# Main_board.net
KiCad netlist of a schematic drawn in EAGLE
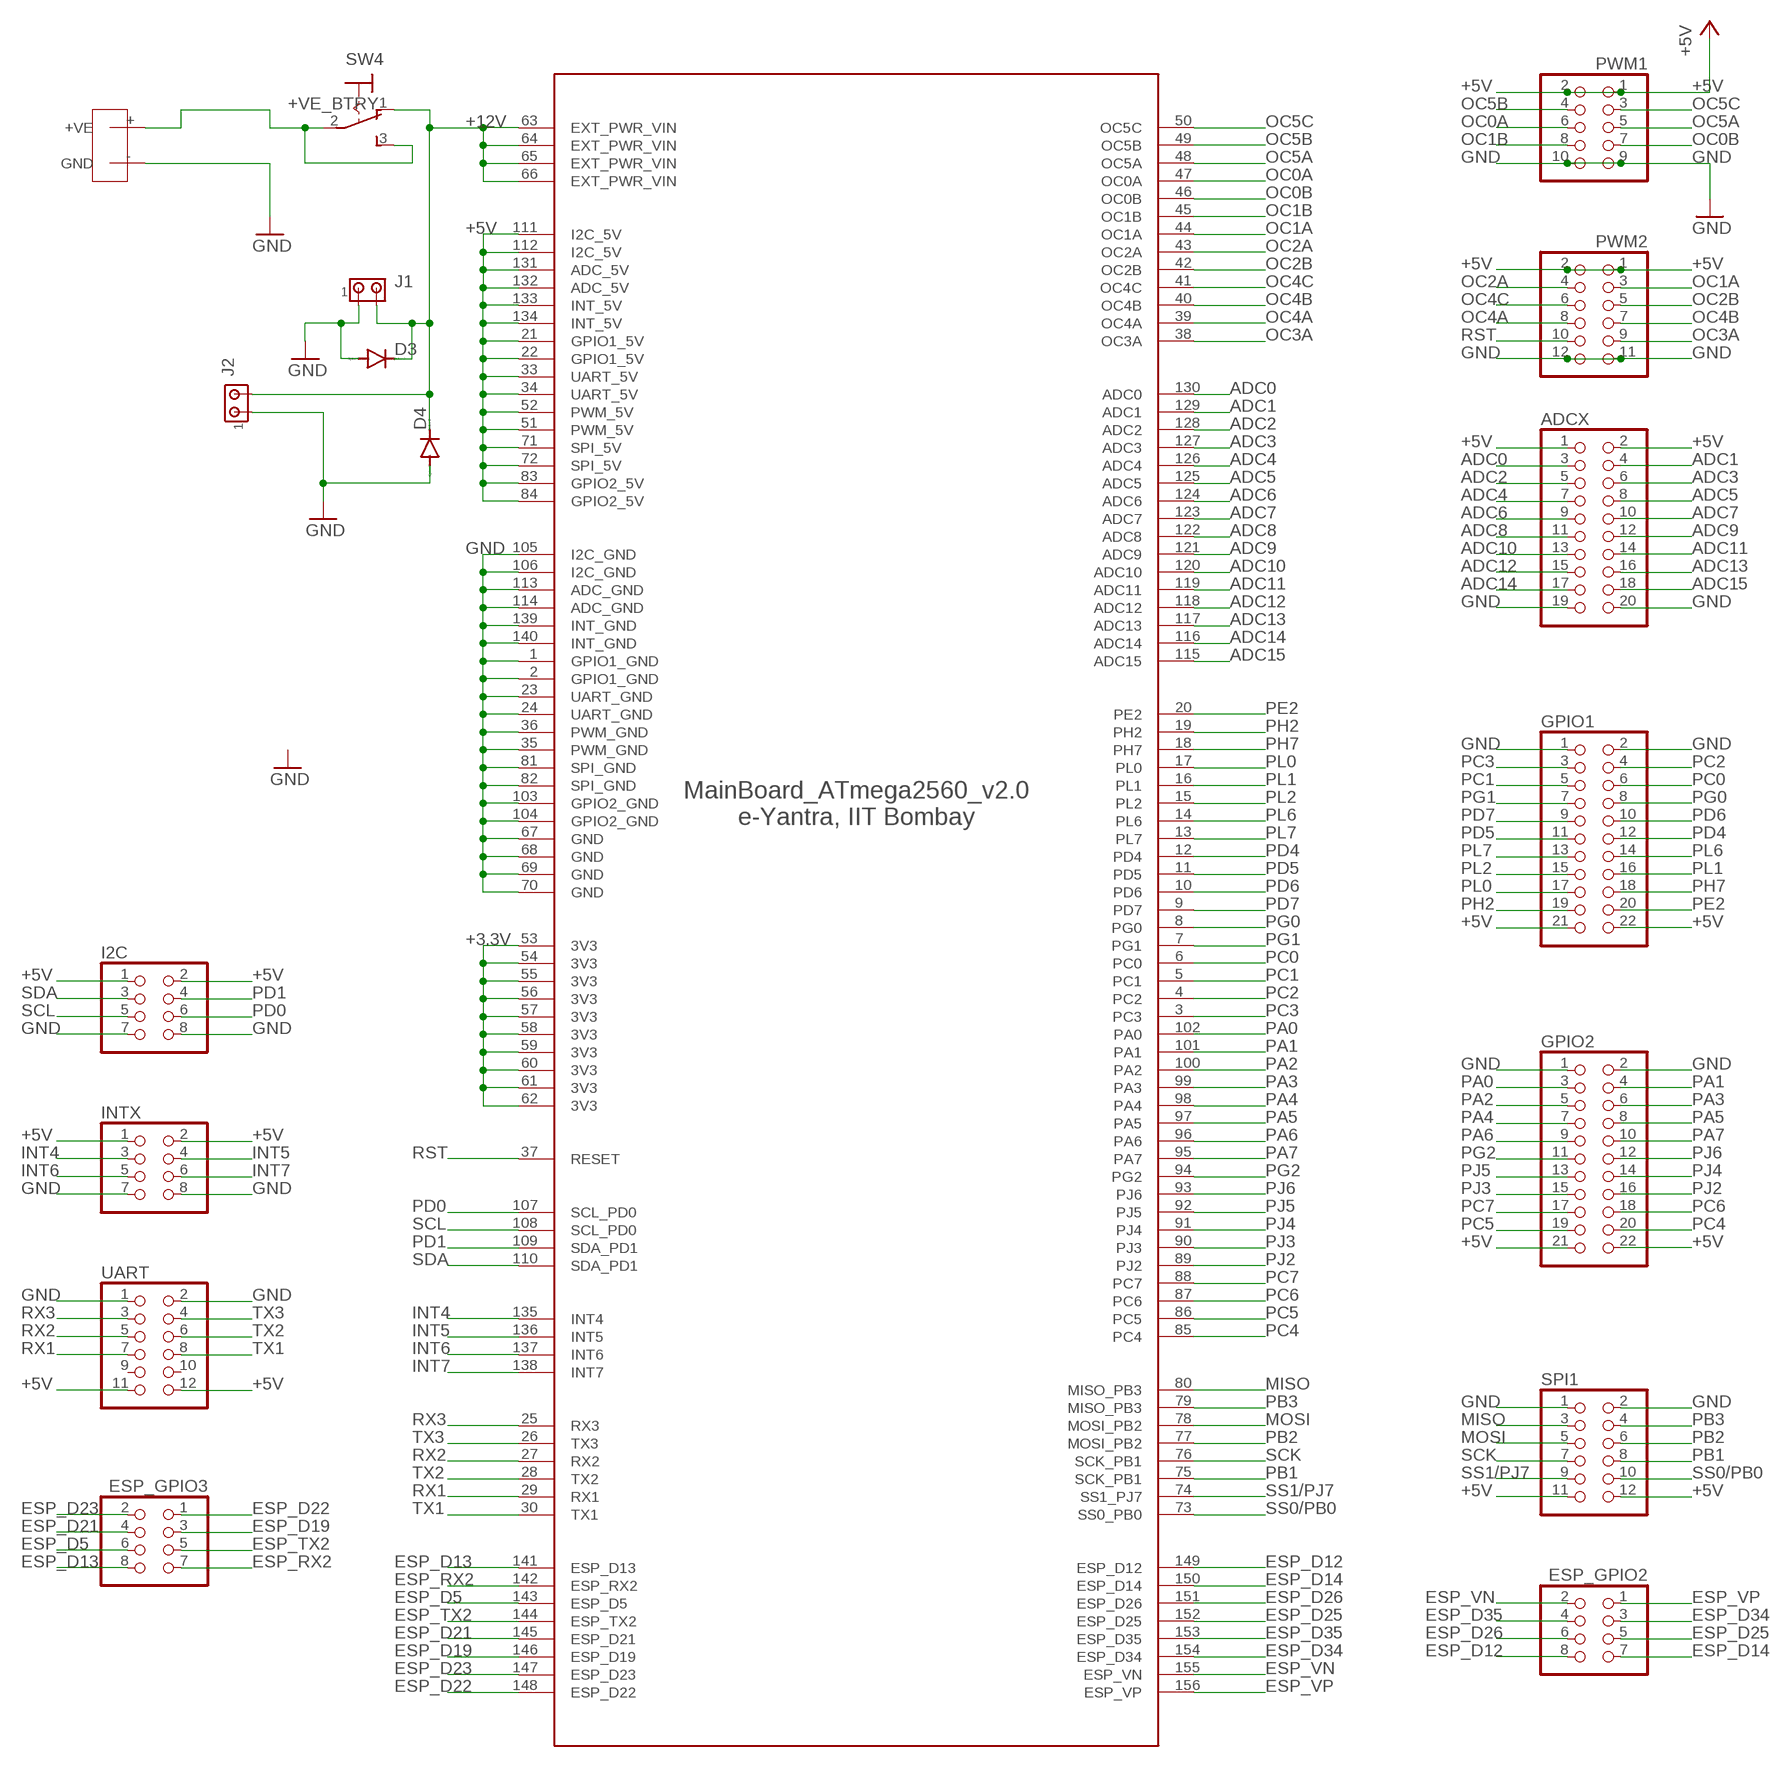
[diagram p0: schematic, sheet 1]
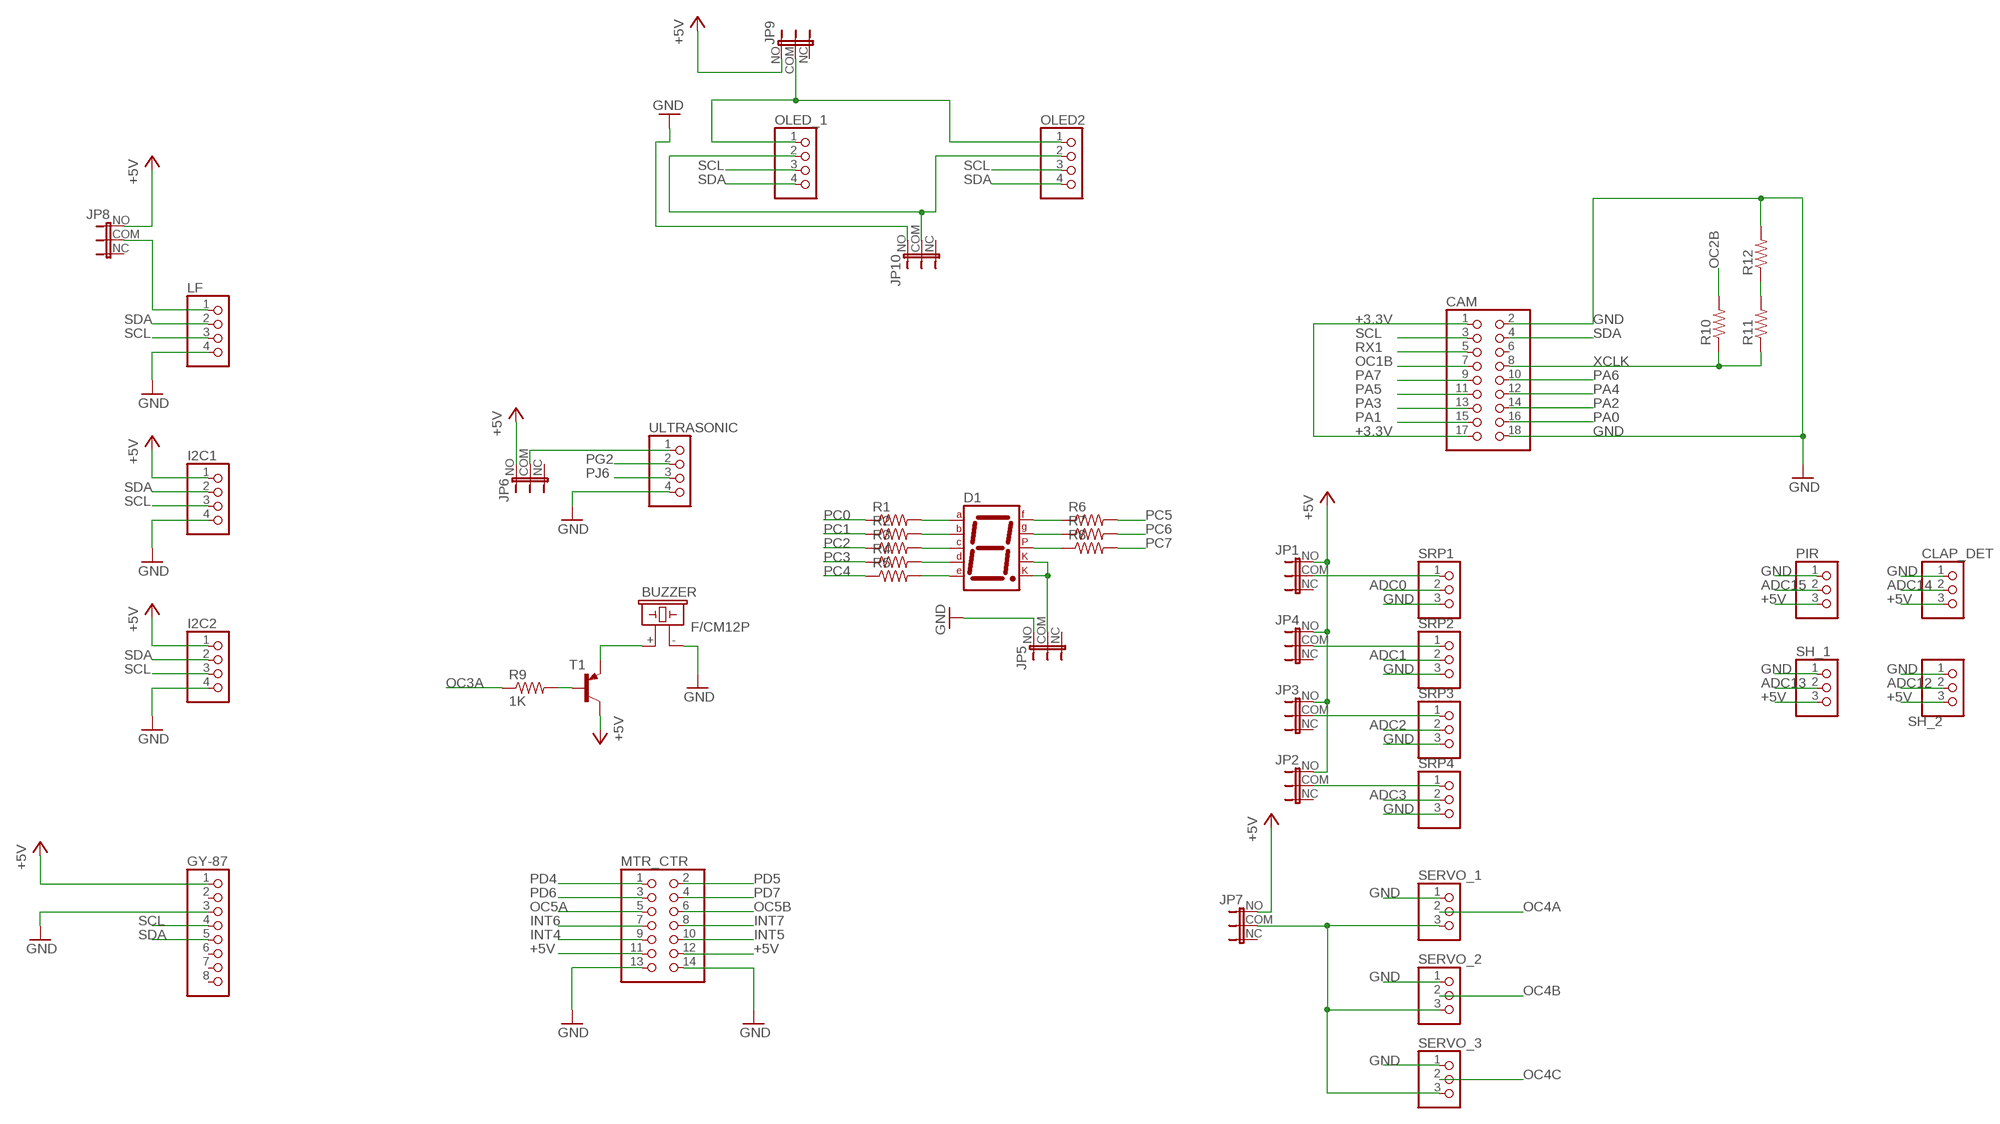
[diagram p1: schematic, sheet 2]

(export (version "E")
  (design (tool "Eeschema 10.0.6"))
  (components
    (comp (ref "BUZZER")
      (value "F/CM12P")
      (footprint "eagle-import:F_CM12P")
      (libsource (lib "eagle-import") (part "F/CM12P"))
    )
    (comp (ref "CAM")
      (value "PINHD-2X9")
      (footprint "eagle-import:2X09")
      (libsource (lib "eagle-import") (part "PINHD-2X9"))
    )
    (comp (ref "CLAP_DET")
      (value "PINHD-1X3")
      (footprint "eagle-import:1X03")
      (libsource (lib "eagle-import") (part "pinhead_325_PINHD-1X3"))
    )
    (comp (ref "D1")
      (value "7SEG-CK")
      (footprint "eagle-import:7SEG-13")
      (libsource (lib "eagle-import") (part "7SEG-CK"))
    )
    (comp (ref "GY-87")
      (value "PINHD-1X8")
      (footprint "eagle-import:1X08")
      (libsource (lib "eagle-import") (part "PINHD-1X8"))
    )
    (comp (ref "I2C1")
      (value "PINHD-1X4")
      (footprint "eagle-import:1X04")
      (libsource (lib "eagle-import") (part "PINHD-1X4"))
    )
    (comp (ref "I2C2")
      (value "PINHD-1X4")
      (footprint "eagle-import:1X04")
      (libsource (lib "eagle-import") (part "PINHD-1X4"))
    )
    (comp (ref "JP1")
      (value "JP2E")
      (footprint "eagle-import:JP2")
      (libsource (lib "eagle-import") (part "JP2E"))
    )
    (comp (ref "JP2")
      (value "JP2E")
      (footprint "eagle-import:JP2")
      (libsource (lib "eagle-import") (part "JP2E"))
    )
    (comp (ref "JP3")
      (value "JP2E")
      (footprint "eagle-import:JP2")
      (libsource (lib "eagle-import") (part "JP2E"))
    )
    (comp (ref "JP4")
      (value "JP2E")
      (footprint "eagle-import:JP2")
      (libsource (lib "eagle-import") (part "JP2E"))
    )
    (comp (ref "JP5")
      (value "JP2E")
      (footprint "eagle-import:JP2")
      (libsource (lib "eagle-import") (part "JP2E"))
    )
    (comp (ref "JP6")
      (value "JP2E")
      (footprint "eagle-import:JP2")
      (libsource (lib "eagle-import") (part "JP2E"))
    )
    (comp (ref "JP7")
      (value "JP2E")
      (footprint "eagle-import:JP2")
      (libsource (lib "eagle-import") (part "JP2E"))
    )
    (comp (ref "JP8")
      (value "JP2E")
      (footprint "eagle-import:JP2")
      (libsource (lib "eagle-import") (part "JP2E"))
    )
    (comp (ref "JP9")
      (value "JP2E")
      (footprint "eagle-import:JP2")
      (libsource (lib "eagle-import") (part "JP2E"))
    )
    (comp (ref "JP10")
      (value "JP2E")
      (footprint "eagle-import:JP2")
      (libsource (lib "eagle-import") (part "JP2E"))
    )
    (comp (ref "LF")
      (value "PINHD-1X4")
      (footprint "eagle-import:1X04")
      (libsource (lib "eagle-import") (part "PINHD-1X4"))
    )
    (comp (ref "MTR_CTR")
      (value "PINHD-2X7")
      (footprint "eagle-import:2X07")
      (libsource (lib "eagle-import") (part "PINHD-2X7"))
    )
    (comp (ref "OLED2")
      (value "PINHD-1X4")
      (footprint "eagle-import:1X04")
      (libsource (lib "eagle-import") (part "PINHD-1X4"))
    )
    (comp (ref "OLED_1")
      (value "PINHD-1X4")
      (footprint "eagle-import:1X04")
      (libsource (lib "eagle-import") (part "PINHD-1X4"))
    )
    (comp (ref "PIR")
      (value "PINHD-1X3")
      (footprint "eagle-import:1X03")
      (libsource (lib "eagle-import") (part "pinhead_325_PINHD-1X3"))
    )
    (comp (ref "R1")
      (value "R-US_R1206")
      (footprint "eagle-import:R1206")
      (libsource (lib "eagle-import") (part "R-US_R1206"))
    )
    (comp (ref "R2")
      (value "R-US_R1206")
      (footprint "eagle-import:R1206")
      (libsource (lib "eagle-import") (part "R-US_R1206"))
    )
    (comp (ref "R3")
      (value "R-US_R1206")
      (footprint "eagle-import:R1206")
      (libsource (lib "eagle-import") (part "R-US_R1206"))
    )
    (comp (ref "R4")
      (value "R-US_R1206")
      (footprint "eagle-import:R1206")
      (libsource (lib "eagle-import") (part "R-US_R1206"))
    )
    (comp (ref "R5")
      (value "R-US_R1206")
      (footprint "eagle-import:R1206")
      (libsource (lib "eagle-import") (part "R-US_R1206"))
    )
    (comp (ref "R6")
      (value "R-US_R1206")
      (footprint "eagle-import:R1206")
      (libsource (lib "eagle-import") (part "R-US_R1206"))
    )
    (comp (ref "R7")
      (value "R-US_R1206")
      (footprint "eagle-import:R1206")
      (libsource (lib "eagle-import") (part "R-US_R1206"))
    )
    (comp (ref "R8")
      (value "R-US_R1206")
      (footprint "eagle-import:R1206")
      (libsource (lib "eagle-import") (part "R-US_R1206"))
    )
    (comp (ref "R9")
      (value "1K")
      (footprint "eagle-import:R1206")
      (libsource (lib "eagle-import") (part "R-US_R1206"))
    )
    (comp (ref "R10")
      (value "R-US_R1206")
      (footprint "eagle-import:R1206")
      (libsource (lib "eagle-import") (part "R-US_R1206"))
    )
    (comp (ref "R11")
      (value "R-US_R1206")
      (footprint "eagle-import:R1206")
      (libsource (lib "eagle-import") (part "R-US_R1206"))
    )
    (comp (ref "R12")
      (value "R-US_R1206")
      (footprint "eagle-import:R1206")
      (libsource (lib "eagle-import") (part "R-US_R1206"))
    )
    (comp (ref "SERVO_1")
      (value "PINHD-1X3")
      (footprint "eagle-import:1X03")
      (libsource (lib "eagle-import") (part "pinhead_325_PINHD-1X3"))
    )
    (comp (ref "SERVO_2")
      (value "PINHD-1X3")
      (footprint "eagle-import:1X03")
      (libsource (lib "eagle-import") (part "pinhead_325_PINHD-1X3"))
    )
    (comp (ref "SERVO_3")
      (value "PINHD-1X3")
      (footprint "eagle-import:1X03")
      (libsource (lib "eagle-import") (part "pinhead_325_PINHD-1X3"))
    )
    (comp (ref "SH_1")
      (value "PINHD-1X3")
      (footprint "eagle-import:1X03")
      (libsource (lib "eagle-import") (part "pinhead_325_PINHD-1X3"))
    )
    (comp (ref "SH_2")
      (value "PINHD-1X3")
      (footprint "eagle-import:1X03")
      (libsource (lib "eagle-import") (part "pinhead_325_PINHD-1X3"))
    )
    (comp (ref "SRP1")
      (value "PINHD-1X3")
      (footprint "eagle-import:1X03")
      (libsource (lib "eagle-import") (part "PINHD-1X3"))
    )
    (comp (ref "SRP2")
      (value "PINHD-1X3")
      (footprint "eagle-import:1X03")
      (libsource (lib "eagle-import") (part "PINHD-1X3"))
    )
    (comp (ref "SRP3")
      (value "PINHD-1X3")
      (footprint "eagle-import:1X03")
      (libsource (lib "eagle-import") (part "PINHD-1X3"))
    )
    (comp (ref "SRP4")
      (value "PINHD-1X3")
      (footprint "eagle-import:1X03")
      (libsource (lib "eagle-import") (part "PINHD-1X3"))
    )
    (comp (ref "T1")
      (value "BC807-16-PNP-SOT23-BEC")
      (footprint "eagle-import:SOT23-BEC")
      (libsource (lib "eagle-import") (part "-PNP-SOT23-BECBC807-16"))
    )
    (comp (ref "ULTRASONIC")
      (value "PINHD-1X4")
      (footprint "eagle-import:1X04")
      (libsource (lib "eagle-import") (part "PINHD-1X4"))
    )
    (comp (ref "ADCX")
      (value "PINHD-2X10")
      (footprint "eagle-import:2X10")
      (libsource (lib "eagle-import") (part "PINHD-2X10"))
    )
    (comp (ref "D3")
      (value "DIODE-DO214AC")
      (footprint "eagle-import:DO214AC")
      (libsource (lib "eagle-import") (part "DIODE-DO214AC"))
    )
    (comp (ref "D4")
      (value "DIODE-DO214AC")
      (footprint "eagle-import:DO214AC")
      (libsource (lib "eagle-import") (part "DIODE-DO214AC"))
    )
    (comp (ref "ESP_GPIO2")
      (value "PINHD-2X4")
      (footprint "eagle-import:2X04")
      (libsource (lib "eagle-import") (part "PINHD-2X4"))
    )
    (comp (ref "ESP_GPIO3")
      (value "PINHD-2X4")
      (footprint "eagle-import:2X04")
      (libsource (lib "eagle-import") (part "PINHD-2X4"))
    )
    (comp (ref "EYFI_MEGA")
      (value "ATMEGA2560_V2.0")
      (footprint "eagle-import:ATMEGA2560_V2.0")
      (libsource (lib "eagle-import") (part "ATMEGA2560_V2.0"))
    )
    (comp (ref "GPIO1")
      (value "PINHD-2X11")
      (footprint "eagle-import:2X11")
      (libsource (lib "eagle-import") (part "PINHD-2X11"))
    )
    (comp (ref "GPIO2")
      (value "PINHD-2X11")
      (footprint "eagle-import:2X11")
      (libsource (lib "eagle-import") (part "PINHD-2X11"))
    )
    (comp (ref "I2C")
      (value "PINHD-2X4")
      (footprint "eagle-import:2X04")
      (libsource (lib "eagle-import") (part "PINHD-2X4"))
    )
    (comp (ref "INTX")
      (value "PINHD-2X4")
      (footprint "eagle-import:2X04")
      (libsource (lib "eagle-import") (part "PINHD-2X4"))
    )
    (comp (ref "J1")
      (value "MTA02-156")
      (footprint "eagle-import:1X2MTA")
      (libsource (lib "eagle-import") (part "MTA02-156"))
    )
    (comp (ref "J2")
      (value "MTA02-156")
      (footprint "eagle-import:1X2MTA")
      (libsource (lib "eagle-import") (part "MTA02-156"))
    )
    (comp (ref "PWM1")
      (value "PINHD-2X5")
      (footprint "eagle-import:2X05")
      (libsource (lib "eagle-import") (part "PINHD-2X5"))
    )
    (comp (ref "PWM2")
      (value "PINHD-2X6")
      (footprint "eagle-import:2X06")
      (libsource (lib "eagle-import") (part "PINHD-2X6"))
    )
    (comp (ref "SPI1")
      (value "PINHD-2X6")
      (footprint "eagle-import:2X06")
      (libsource (lib "eagle-import") (part "PINHD-2X6"))
    )
    (comp (ref "SW4")
      (value "M9040P")
      (footprint "eagle-import:M9040P")
      (libsource (lib "eagle-import") (part "M9040P"))
    )
    (comp (ref "U$1")
      (value "DEANS")
      (footprint "eagle-import:DEANS")
      (libsource (lib "eagle-import") (part "DEANS"))
    )
    (comp (ref "UART")
      (value "PINHD-2X6")
      (footprint "eagle-import:2X06")
      (libsource (lib "eagle-import") (part "PINHD-2X6"))
    )
  )
  (nets
    (net (code "1") (name "+3.3V") (class "Default")
      (node (ref "CAM") (pin "1") (pinfunction "1_1") (pintype "passive"))
      (node (ref "CAM") (pin "17") (pinfunction "17_17") (pintype "passive"))
      (node (ref "EYFI_MEGA") (pin "53") (pinfunction "3V3_53") (pintype "power_in"))
      (node (ref "EYFI_MEGA") (pin "54") (pinfunction "3V3_54") (pintype "power_in"))
      (node (ref "EYFI_MEGA") (pin "55") (pinfunction "3V3_55") (pintype "power_in"))
      (node (ref "EYFI_MEGA") (pin "56") (pinfunction "3V3_56") (pintype "power_in"))
      (node (ref "EYFI_MEGA") (pin "57") (pinfunction "3V3_57") (pintype "power_in"))
      (node (ref "EYFI_MEGA") (pin "58") (pinfunction "3V3_58") (pintype "power_in"))
      (node (ref "EYFI_MEGA") (pin "59") (pinfunction "3V3_59") (pintype "power_in"))
      (node (ref "EYFI_MEGA") (pin "60") (pinfunction "3V3_60") (pintype "power_in"))
      (node (ref "EYFI_MEGA") (pin "61") (pinfunction "3V3_61") (pintype "power_in"))
      (node (ref "EYFI_MEGA") (pin "62") (pinfunction "3V3_62") (pintype "power_in"))
    )
    (net (code "2") (name "+5V") (class "Default")
      (node (ref "ADCX") (pin "1") (pinfunction "1_1") (pintype "passive"))
      (node (ref "ADCX") (pin "2") (pinfunction "2_2") (pintype "passive"))
      (node (ref "CLAP_DET") (pin "3") (pinfunction "3_3") (pintype "passive"))
      (node (ref "EYFI_MEGA") (pin "111") (pinfunction "I2C_5V_111") (pintype "power_in"))
      (node (ref "EYFI_MEGA") (pin "112") (pinfunction "I2C_5V_112") (pintype "power_in"))
      (node (ref "EYFI_MEGA") (pin "131") (pinfunction "ADC_5V_131") (pintype "power_in"))
      (node (ref "EYFI_MEGA") (pin "132") (pinfunction "ADC_5V_132") (pintype "power_in"))
      (node (ref "EYFI_MEGA") (pin "133") (pinfunction "INT_5V_133") (pintype "power_in"))
      (node (ref "EYFI_MEGA") (pin "134") (pinfunction "INT_5V_134") (pintype "power_in"))
      (node (ref "EYFI_MEGA") (pin "21") (pinfunction "GPIO1_5V_21") (pintype "power_in"))
      (node (ref "EYFI_MEGA") (pin "22") (pinfunction "GPIO1_5V_22") (pintype "power_in"))
      (node (ref "EYFI_MEGA") (pin "33") (pinfunction "UART_5V_33") (pintype "power_in"))
      (node (ref "EYFI_MEGA") (pin "34") (pinfunction "UART_5V_34") (pintype "power_in"))
      (node (ref "EYFI_MEGA") (pin "51") (pinfunction "PWM_5V_51") (pintype "power_in"))
      (node (ref "EYFI_MEGA") (pin "52") (pinfunction "PWM_5V_52") (pintype "power_in"))
      (node (ref "EYFI_MEGA") (pin "71") (pinfunction "SPI_5V_71") (pintype "power_in"))
      (node (ref "EYFI_MEGA") (pin "72") (pinfunction "SPI_5V_72") (pintype "power_in"))
      (node (ref "EYFI_MEGA") (pin "83") (pinfunction "GPIO2_5V_83") (pintype "power_in"))
      (node (ref "EYFI_MEGA") (pin "84") (pinfunction "GPIO2_5V_84") (pintype "power_in"))
      (node (ref "GPIO1") (pin "21") (pinfunction "21_21") (pintype "passive"))
      (node (ref "GPIO1") (pin "22") (pinfunction "22_22") (pintype "passive"))
      (node (ref "GPIO2") (pin "21") (pinfunction "21_21") (pintype "passive"))
      (node (ref "GPIO2") (pin "22") (pinfunction "22_22") (pintype "passive"))
      (node (ref "GY-87") (pin "1") (pinfunction "1_1") (pintype "passive"))
      (node (ref "I2C") (pin "1") (pinfunction "1_1") (pintype "passive"))
      (node (ref "I2C") (pin "2") (pinfunction "2_2") (pintype "passive"))
      (node (ref "I2C1") (pin "1") (pinfunction "1_1") (pintype "passive"))
      (node (ref "I2C2") (pin "1") (pinfunction "1_1") (pintype "passive"))
      (node (ref "INTX") (pin "1") (pinfunction "1_1") (pintype "passive"))
      (node (ref "INTX") (pin "2") (pinfunction "2_2") (pintype "passive"))
      (node (ref "JP1") (pin "NO") (pinfunction "1_NO") (pintype "passive"))
      (node (ref "JP2") (pin "NO") (pinfunction "1_NO") (pintype "passive"))
      (node (ref "JP3") (pin "NO") (pinfunction "1_NO") (pintype "passive"))
      (node (ref "JP4") (pin "NO") (pinfunction "1_NO") (pintype "passive"))
      (node (ref "JP6") (pin "NO") (pinfunction "1_NO") (pintype "passive"))
      (node (ref "JP7") (pin "NO") (pinfunction "1_NO") (pintype "passive"))
      (node (ref "JP8") (pin "NO") (pinfunction "1_NO") (pintype "passive"))
      (node (ref "JP9") (pin "NO") (pinfunction "1_NO") (pintype "passive"))
      (node (ref "MTR_CTR") (pin "11") (pinfunction "11_11") (pintype "passive"))
      (node (ref "MTR_CTR") (pin "12") (pinfunction "12_12") (pintype "passive"))
      (node (ref "PIR") (pin "3") (pinfunction "3_3") (pintype "passive"))
      (node (ref "PWM1") (pin "1") (pinfunction "1_1") (pintype "passive"))
      (node (ref "PWM1") (pin "2") (pinfunction "2_2") (pintype "passive"))
      (node (ref "PWM2") (pin "1") (pinfunction "1_1") (pintype "passive"))
      (node (ref "PWM2") (pin "2") (pinfunction "2_2") (pintype "passive"))
      (node (ref "SH_1") (pin "3") (pinfunction "3_3") (pintype "passive"))
      (node (ref "SH_2") (pin "3") (pinfunction "3_3") (pintype "passive"))
      (node (ref "SPI1") (pin "11") (pinfunction "11_11") (pintype "passive"))
      (node (ref "SPI1") (pin "12") (pinfunction "12_12") (pintype "passive"))
      (node (ref "T1") (pin "C") (pinfunction "C_C") (pintype "passive"))
      (node (ref "UART") (pin "11") (pinfunction "11_11") (pintype "passive"))
      (node (ref "UART") (pin "12") (pinfunction "12_12") (pintype "passive"))
    )
    (net (code "3") (name "+12V") (class "Default")
      (node (ref "D3") (pin "C") (pinfunction "C_C") (pintype "passive"))
      (node (ref "D4") (pin "C") (pinfunction "C_C") (pintype "passive"))
      (node (ref "EYFI_MEGA") (pin "63") (pinfunction "EXT_PWR_VIN_63") (pintype "power_in"))
      (node (ref "EYFI_MEGA") (pin "64") (pinfunction "EXT_PWR_VIN_64") (pintype "power_in"))
      (node (ref "EYFI_MEGA") (pin "65") (pinfunction "EXT_PWR_VIN_65") (pintype "power_in"))
      (node (ref "EYFI_MEGA") (pin "66") (pinfunction "EXT_PWR_VIN_66") (pintype "power_in"))
      (node (ref "J1") (pin "2") (pinfunction "2_2") (pintype "passive"))
      (node (ref "J2") (pin "2") (pinfunction "2_2") (pintype "passive"))
      (node (ref "SW4") (pin "1") (pinfunction "O_1") (pintype "passive"))
    )
    (net (code "4") (name "+VE_BTRY") (class "Default")
      (node (ref "SW4") (pin "2") (pinfunction "P_2") (pintype "passive"))
      (node (ref "SW4") (pin "3") (pinfunction "S_3") (pintype "passive"))
      (node (ref "U$1") (pin "+") (pinfunction "+VE_+") (pintype "bidirectional"))
    )
    (net (code "5") (name "ADC0") (class "Default")
      (node (ref "ADCX") (pin "3") (pinfunction "3_3") (pintype "passive"))
      (node (ref "EYFI_MEGA") (pin "130") (pinfunction "ADC0_130") (pintype "bidirectional"))
      (node (ref "SRP1") (pin "2") (pinfunction "2_2") (pintype "passive"))
    )
    (net (code "6") (name "ADC1") (class "Default")
      (node (ref "ADCX") (pin "4") (pinfunction "4_4") (pintype "passive"))
      (node (ref "EYFI_MEGA") (pin "129") (pinfunction "ADC1_129") (pintype "bidirectional"))
      (node (ref "SRP2") (pin "2") (pinfunction "2_2") (pintype "passive"))
    )
    (net (code "7") (name "ADC2") (class "Default")
      (node (ref "ADCX") (pin "5") (pinfunction "5_5") (pintype "passive"))
      (node (ref "EYFI_MEGA") (pin "128") (pinfunction "ADC2_128") (pintype "bidirectional"))
      (node (ref "SRP3") (pin "2") (pinfunction "2_2") (pintype "passive"))
    )
    (net (code "8") (name "ADC3") (class "Default")
      (node (ref "ADCX") (pin "6") (pinfunction "6_6") (pintype "passive"))
      (node (ref "EYFI_MEGA") (pin "127") (pinfunction "ADC3_127") (pintype "bidirectional"))
      (node (ref "SRP4") (pin "2") (pinfunction "2_2") (pintype "passive"))
    )
    (net (code "9") (name "ADC4") (class "Default")
      (node (ref "ADCX") (pin "7") (pinfunction "7_7") (pintype "passive"))
      (node (ref "EYFI_MEGA") (pin "126") (pinfunction "ADC4_126") (pintype "bidirectional"))
    )
    (net (code "10") (name "ADC5") (class "Default")
      (node (ref "ADCX") (pin "8") (pinfunction "8_8") (pintype "passive"))
      (node (ref "EYFI_MEGA") (pin "125") (pinfunction "ADC5_125") (pintype "bidirectional"))
    )
    (net (code "11") (name "ADC6") (class "Default")
      (node (ref "ADCX") (pin "9") (pinfunction "9_9") (pintype "passive"))
      (node (ref "EYFI_MEGA") (pin "124") (pinfunction "ADC6_124") (pintype "bidirectional"))
    )
    (net (code "12") (name "ADC7") (class "Default")
      (node (ref "ADCX") (pin "10") (pinfunction "10_10") (pintype "passive"))
      (node (ref "EYFI_MEGA") (pin "123") (pinfunction "ADC7_123") (pintype "bidirectional"))
    )
    (net (code "13") (name "ADC8") (class "Default")
      (node (ref "ADCX") (pin "11") (pinfunction "11_11") (pintype "passive"))
      (node (ref "EYFI_MEGA") (pin "122") (pinfunction "ADC8_122") (pintype "bidirectional"))
    )
    (net (code "14") (name "ADC9") (class "Default")
      (node (ref "ADCX") (pin "12") (pinfunction "12_12") (pintype "passive"))
      (node (ref "EYFI_MEGA") (pin "121") (pinfunction "ADC9_121") (pintype "bidirectional"))
    )
    (net (code "15") (name "ADC10") (class "Default")
      (node (ref "ADCX") (pin "13") (pinfunction "13_13") (pintype "passive"))
      (node (ref "EYFI_MEGA") (pin "120") (pinfunction "ADC10_120") (pintype "bidirectional"))
    )
    (net (code "16") (name "ADC11") (class "Default")
      (node (ref "ADCX") (pin "14") (pinfunction "14_14") (pintype "passive"))
      (node (ref "EYFI_MEGA") (pin "119") (pinfunction "ADC11_119") (pintype "bidirectional"))
    )
    (net (code "17") (name "ADC12") (class "Default")
      (node (ref "ADCX") (pin "15") (pinfunction "15_15") (pintype "passive"))
      (node (ref "EYFI_MEGA") (pin "118") (pinfunction "ADC12_118") (pintype "bidirectional"))
      (node (ref "SH_2") (pin "2") (pinfunction "2_2") (pintype "passive"))
    )
    (net (code "18") (name "ADC13") (class "Default")
      (node (ref "ADCX") (pin "16") (pinfunction "16_16") (pintype "passive"))
      (node (ref "EYFI_MEGA") (pin "117") (pinfunction "ADC13_117") (pintype "bidirectional"))
      (node (ref "SH_1") (pin "2") (pinfunction "2_2") (pintype "passive"))
    )
    (net (code "19") (name "ADC14") (class "Default")
      (node (ref "ADCX") (pin "17") (pinfunction "17_17") (pintype "passive"))
      (node (ref "CLAP_DET") (pin "2") (pinfunction "2_2") (pintype "passive"))
      (node (ref "EYFI_MEGA") (pin "116") (pinfunction "ADC14_116") (pintype "bidirectional"))
    )
    (net (code "20") (name "ADC15") (class "Default")
      (node (ref "ADCX") (pin "18") (pinfunction "18_18") (pintype "passive"))
      (node (ref "EYFI_MEGA") (pin "115") (pinfunction "ADC15_115") (pintype "bidirectional"))
      (node (ref "PIR") (pin "2") (pinfunction "2_2") (pintype "passive"))
    )
    (net (code "21") (name "ESP_D5") (class "Default")
      (node (ref "ESP_GPIO3") (pin "6") (pinfunction "6_6") (pintype "passive"))
      (node (ref "EYFI_MEGA") (pin "143") (pinfunction "ESP_D5_143") (pintype "bidirectional"))
    )
    (net (code "22") (name "ESP_D12") (class "Default")
      (node (ref "ESP_GPIO2") (pin "8") (pinfunction "8_8") (pintype "passive"))
      (node (ref "EYFI_MEGA") (pin "149") (pinfunction "ESP_D12_149") (pintype "bidirectional"))
    )
    (net (code "23") (name "ESP_D13") (class "Default")
      (node (ref "ESP_GPIO3") (pin "8") (pinfunction "8_8") (pintype "passive"))
      (node (ref "EYFI_MEGA") (pin "141") (pinfunction "ESP_D13_141") (pintype "bidirectional"))
    )
    (net (code "24") (name "ESP_D14") (class "Default")
      (node (ref "ESP_GPIO2") (pin "7") (pinfunction "7_7") (pintype "passive"))
      (node (ref "EYFI_MEGA") (pin "150") (pinfunction "ESP_D14_150") (pintype "bidirectional"))
    )
    (net (code "25") (name "ESP_D19") (class "Default")
      (node (ref "ESP_GPIO3") (pin "3") (pinfunction "3_3") (pintype "passive"))
      (node (ref "EYFI_MEGA") (pin "146") (pinfunction "ESP_D19_146") (pintype "bidirectional"))
    )
    (net (code "26") (name "ESP_D21") (class "Default")
      (node (ref "ESP_GPIO3") (pin "4") (pinfunction "4_4") (pintype "passive"))
      (node (ref "EYFI_MEGA") (pin "145") (pinfunction "ESP_D21_145") (pintype "bidirectional"))
    )
    (net (code "27") (name "ESP_D22") (class "Default")
      (node (ref "ESP_GPIO3") (pin "1") (pinfunction "1_1") (pintype "passive"))
      (node (ref "EYFI_MEGA") (pin "148") (pinfunction "ESP_D22_148") (pintype "bidirectional"))
    )
    (net (code "28") (name "ESP_D23") (class "Default")
      (node (ref "ESP_GPIO3") (pin "2") (pinfunction "2_2") (pintype "passive"))
      (node (ref "EYFI_MEGA") (pin "147") (pinfunction "ESP_D23_147") (pintype "bidirectional"))
    )
    (net (code "29") (name "ESP_D25") (class "Default")
      (node (ref "ESP_GPIO2") (pin "5") (pinfunction "5_5") (pintype "passive"))
      (node (ref "EYFI_MEGA") (pin "152") (pinfunction "ESP_D25_152") (pintype "bidirectional"))
    )
    (net (code "30") (name "ESP_D26") (class "Default")
      (node (ref "ESP_GPIO2") (pin "6") (pinfunction "6_6") (pintype "passive"))
      (node (ref "EYFI_MEGA") (pin "151") (pinfunction "ESP_D26_151") (pintype "bidirectional"))
    )
    (net (code "31") (name "ESP_D34") (class "Default")
      (node (ref "ESP_GPIO2") (pin "3") (pinfunction "3_3") (pintype "passive"))
      (node (ref "EYFI_MEGA") (pin "154") (pinfunction "ESP_D34_154") (pintype "bidirectional"))
    )
    (net (code "32") (name "ESP_D35") (class "Default")
      (node (ref "ESP_GPIO2") (pin "4") (pinfunction "4_4") (pintype "passive"))
      (node (ref "EYFI_MEGA") (pin "153") (pinfunction "ESP_D35_153") (pintype "bidirectional"))
    )
    (net (code "33") (name "ESP_RX2") (class "Default")
      (node (ref "ESP_GPIO3") (pin "7") (pinfunction "7_7") (pintype "passive"))
      (node (ref "EYFI_MEGA") (pin "142") (pinfunction "ESP_RX2_142") (pintype "bidirectional"))
    )
    (net (code "34") (name "ESP_TX2") (class "Default")
      (node (ref "ESP_GPIO3") (pin "5") (pinfunction "5_5") (pintype "passive"))
      (node (ref "EYFI_MEGA") (pin "144") (pinfunction "ESP_TX2_144") (pintype "bidirectional"))
    )
    (net (code "35") (name "ESP_VN") (class "Default")
      (node (ref "ESP_GPIO2") (pin "2") (pinfunction "2_2") (pintype "passive"))
      (node (ref "EYFI_MEGA") (pin "155") (pinfunction "ESP_VN_155") (pintype "bidirectional"))
    )
    (net (code "36") (name "ESP_VP") (class "Default")
      (node (ref "ESP_GPIO2") (pin "1") (pinfunction "1_1") (pintype "passive"))
      (node (ref "EYFI_MEGA") (pin "156") (pinfunction "ESP_VP_156") (pintype "bidirectional"))
    )
    (net (code "37") (name "GND") (class "Default")
      (node (ref "ADCX") (pin "19") (pinfunction "19_19") (pintype "passive"))
      (node (ref "ADCX") (pin "20") (pinfunction "20_20") (pintype "passive"))
      (node (ref "BUZZER") (pin "-") (pinfunction "2_-") (pintype "passive"))
      (node (ref "CAM") (pin "18") (pinfunction "18_18") (pintype "passive"))
      (node (ref "CAM") (pin "2") (pinfunction "2_2") (pintype "passive"))
      (node (ref "CLAP_DET") (pin "1") (pinfunction "1_1") (pintype "passive"))
      (node (ref "D3") (pin "A") (pinfunction "A_A") (pintype "passive"))
      (node (ref "D4") (pin "A") (pinfunction "A_A") (pintype "passive"))
      (node (ref "EYFI_MEGA") (pin "1") (pinfunction "GPIO1_GND_1") (pintype "power_in"))
      (node (ref "EYFI_MEGA") (pin "103") (pinfunction "GPIO2_GND_103") (pintype "power_in"))
      (node (ref "EYFI_MEGA") (pin "104") (pinfunction "GPIO2_GND_104") (pintype "power_in"))
      (node (ref "EYFI_MEGA") (pin "105") (pinfunction "I2C_GND_105") (pintype "power_in"))
      (node (ref "EYFI_MEGA") (pin "106") (pinfunction "I2C_GND_106") (pintype "power_in"))
      (node (ref "EYFI_MEGA") (pin "113") (pinfunction "ADC_GND_113") (pintype "power_in"))
      (node (ref "EYFI_MEGA") (pin "114") (pinfunction "ADC_GND_114") (pintype "power_in"))
      (node (ref "EYFI_MEGA") (pin "139") (pinfunction "INT_GND_139") (pintype "power_in"))
      (node (ref "EYFI_MEGA") (pin "140") (pinfunction "INT_GND_140") (pintype "power_in"))
      (node (ref "EYFI_MEGA") (pin "2") (pinfunction "GPIO1_GND_2") (pintype "power_in"))
      (node (ref "EYFI_MEGA") (pin "23") (pinfunction "UART_GND_23") (pintype "power_in"))
      (node (ref "EYFI_MEGA") (pin "24") (pinfunction "UART_GND_24") (pintype "power_in"))
      (node (ref "EYFI_MEGA") (pin "35") (pinfunction "PWM_GND_35") (pintype "power_in"))
      (node (ref "EYFI_MEGA") (pin "36") (pinfunction "PWM_GND_36") (pintype "power_in"))
      (node (ref "EYFI_MEGA") (pin "67") (pinfunction "GND_67") (pintype "power_in"))
      (node (ref "EYFI_MEGA") (pin "68") (pinfunction "GND_68") (pintype "power_in"))
      (node (ref "EYFI_MEGA") (pin "69") (pinfunction "GND_69") (pintype "power_in"))
      (node (ref "EYFI_MEGA") (pin "70") (pinfunction "GND_70") (pintype "power_in"))
      (node (ref "EYFI_MEGA") (pin "81") (pinfunction "SPI_GND_81") (pintype "power_in"))
      (node (ref "EYFI_MEGA") (pin "82") (pinfunction "SPI_GND_82") (pintype "power_in"))
      (node (ref "GPIO1") (pin "1") (pinfunction "1_1") (pintype "passive"))
      (node (ref "GPIO1") (pin "2") (pinfunction "2_2") (pintype "passive"))
      (node (ref "GPIO2") (pin "1") (pinfunction "1_1") (pintype "passive"))
      (node (ref "GPIO2") (pin "2") (pinfunction "2_2") (pintype "passive"))
      (node (ref "GY-87") (pin "3") (pinfunction "3_3") (pintype "passive"))
      (node (ref "I2C") (pin "7") (pinfunction "7_7") (pintype "passive"))
      (node (ref "I2C") (pin "8") (pinfunction "8_8") (pintype "passive"))
      (node (ref "I2C1") (pin "4") (pinfunction "4_4") (pintype "passive"))
      (node (ref "I2C2") (pin "4") (pinfunction "4_4") (pintype "passive"))
      (node (ref "INTX") (pin "7") (pinfunction "7_7") (pintype "passive"))
      (node (ref "INTX") (pin "8") (pinfunction "8_8") (pintype "passive"))
      (node (ref "J1") (pin "1") (pinfunction "1_1") (pintype "passive"))
      (node (ref "J2") (pin "1") (pinfunction "1_1") (pintype "passive"))
      (node (ref "JP10") (pin "NO") (pinfunction "1_NO") (pintype "passive"))
      (node (ref "JP5") (pin "NO") (pinfunction "1_NO") (pintype "passive"))
      (node (ref "LF") (pin "4") (pinfunction "4_4") (pintype "passive"))
      (node (ref "MTR_CTR") (pin "13") (pinfunction "13_13") (pintype "passive"))
      (node (ref "MTR_CTR") (pin "14") (pinfunction "14_14") (pintype "passive"))
      (node (ref "PIR") (pin "1") (pinfunction "1_1") (pintype "passive"))
      (node (ref "PWM1") (pin "10") (pinfunction "10_10") (pintype "passive"))
      (node (ref "PWM1") (pin "9") (pinfunction "9_9") (pintype "passive"))
      (node (ref "PWM2") (pin "11") (pinfunction "11_11") (pintype "passive"))
      (node (ref "PWM2") (pin "12") (pinfunction "12_12") (pintype "passive"))
      (node (ref "R12") (pin "2") (pinfunction "2_2") (pintype "passive"))
      (node (ref "SERVO_1") (pin "1") (pinfunction "1_1") (pintype "passive"))
      (node (ref "SERVO_2") (pin "1") (pinfunction "1_1") (pintype "passive"))
      (node (ref "SERVO_3") (pin "1") (pinfunction "1_1") (pintype "passive"))
      (node (ref "SH_1") (pin "1") (pinfunction "1_1") (pintype "passive"))
      (node (ref "SH_2") (pin "1") (pinfunction "1_1") (pintype "passive"))
      (node (ref "SPI1") (pin "1") (pinfunction "1_1") (pintype "passive"))
      (node (ref "SPI1") (pin "2") (pinfunction "2_2") (pintype "passive"))
      (node (ref "SRP1") (pin "3") (pinfunction "3_3") (pintype "passive"))
      (node (ref "SRP2") (pin "3") (pinfunction "3_3") (pintype "passive"))
      (node (ref "SRP3") (pin "3") (pinfunction "3_3") (pintype "passive"))
      (node (ref "SRP4") (pin "3") (pinfunction "3_3") (pintype "passive"))
      (node (ref "U$1") (pin "-") (pinfunction "GND_-") (pintype "bidirectional"))
      (node (ref "UART") (pin "1") (pinfunction "1_1") (pintype "passive"))
      (node (ref "UART") (pin "2") (pinfunction "2_2") (pintype "passive"))
      (node (ref "ULTRASONIC") (pin "4") (pinfunction "4_4") (pintype "passive"))
    )
    (net (code "38") (name "INT4") (class "Default")
      (node (ref "EYFI_MEGA") (pin "135") (pinfunction "INT4_135") (pintype "bidirectional"))
      (node (ref "INTX") (pin "3") (pinfunction "3_3") (pintype "passive"))
      (node (ref "MTR_CTR") (pin "9") (pinfunction "9_9") (pintype "passive"))
    )
    (net (code "39") (name "INT5") (class "Default")
      (node (ref "EYFI_MEGA") (pin "136") (pinfunction "INT5_136") (pintype "bidirectional"))
      (node (ref "INTX") (pin "4") (pinfunction "4_4") (pintype "passive"))
      (node (ref "MTR_CTR") (pin "10") (pinfunction "10_10") (pintype "passive"))
    )
    (net (code "40") (name "INT6") (class "Default")
      (node (ref "EYFI_MEGA") (pin "137") (pinfunction "INT6_137") (pintype "bidirectional"))
      (node (ref "INTX") (pin "5") (pinfunction "5_5") (pintype "passive"))
      (node (ref "MTR_CTR") (pin "7") (pinfunction "7_7") (pintype "passive"))
    )
    (net (code "41") (name "INT7") (class "Default")
      (node (ref "EYFI_MEGA") (pin "138") (pinfunction "INT7_138") (pintype "bidirectional"))
      (node (ref "INTX") (pin "6") (pinfunction "6_6") (pintype "passive"))
      (node (ref "MTR_CTR") (pin "8") (pinfunction "8_8") (pintype "passive"))
    )
    (net (code "42") (name "MISO") (class "Default")
      (node (ref "EYFI_MEGA") (pin "80") (pinfunction "MISO_PB3_80") (pintype "bidirectional"))
      (node (ref "SPI1") (pin "3") (pinfunction "3_3") (pintype "passive"))
    )
    (net (code "43") (name "MOSI") (class "Default")
      (node (ref "EYFI_MEGA") (pin "78") (pinfunction "MOSI_PB2_78") (pintype "bidirectional"))
      (node (ref "SPI1") (pin "5") (pinfunction "5_5") (pintype "passive"))
    )
    (net (code "44") (name "Net-(BUZZER-1)") (class "Default")
      (node (ref "BUZZER") (pin "+") (pinfunction "1_+") (pintype "passive"))
      (node (ref "T1") (pin "E") (pinfunction "E_E") (pintype "passive"))
    )
    (net (code "45") (name "Net-(D1-A)") (class "Default")
      (node (ref "D1") (pin "7") (pinfunction "A_7") (pintype "passive"))
      (node (ref "R1") (pin "2") (pinfunction "2_2") (pintype "passive"))
    )
    (net (code "46") (name "Net-(D1-B)") (class "Default")
      (node (ref "D1") (pin "6") (pinfunction "B_6") (pintype "passive"))
      (node (ref "R2") (pin "2") (pinfunction "2_2") (pintype "passive"))
    )
    (net (code "47") (name "Net-(D1-C)") (class "Default")
      (node (ref "D1") (pin "4") (pinfunction "C_4") (pintype "passive"))
      (node (ref "R3") (pin "2") (pinfunction "2_2") (pintype "passive"))
    )
    (net (code "48") (name "Net-(D1-CK1)") (class "Default")
      (node (ref "D1") (pin "3") (pinfunction "CK1_3") (pintype "passive"))
      (node (ref "D1") (pin "8") (pinfunction "CK2_8") (pintype "passive"))
      (node (ref "JP5") (pin "COM") (pinfunction "2_COM") (pintype "passive"))
    )
    (net (code "49") (name "Net-(D1-D)") (class "Default")
      (node (ref "D1") (pin "2") (pinfunction "D_2") (pintype "passive"))
      (node (ref "R4") (pin "2") (pinfunction "2_2") (pintype "passive"))
    )
    (net (code "50") (name "Net-(D1-DP)") (class "Default")
      (node (ref "D1") (pin "5") (pinfunction "DP_5") (pintype "passive"))
      (node (ref "R8") (pin "1") (pinfunction "1_1") (pintype "passive"))
    )
    (net (code "51") (name "Net-(D1-E)") (class "Default")
      (node (ref "D1") (pin "1") (pinfunction "E_1") (pintype "passive"))
      (node (ref "R5") (pin "2") (pinfunction "2_2") (pintype "passive"))
    )
    (net (code "52") (name "Net-(D1-F)") (class "Default")
      (node (ref "D1") (pin "9") (pinfunction "F_9") (pintype "passive"))
      (node (ref "R6") (pin "1") (pinfunction "1_1") (pintype "passive"))
    )
    (net (code "53") (name "Net-(D1-G)") (class "Default")
      (node (ref "D1") (pin "10") (pinfunction "G_10") (pintype "passive"))
      (node (ref "R7") (pin "1") (pinfunction "1_1") (pintype "passive"))
    )
    (net (code "54") (name "Net-(JP1-2)") (class "Default")
      (node (ref "JP1") (pin "COM") (pinfunction "2_COM") (pintype "passive"))
      (node (ref "SRP1") (pin "1") (pinfunction "1_1") (pintype "passive"))
    )
    (net (code "55") (name "Net-(JP2-2)") (class "Default")
      (node (ref "JP2") (pin "COM") (pinfunction "2_COM") (pintype "passive"))
      (node (ref "SRP4") (pin "1") (pinfunction "1_1") (pintype "passive"))
    )
    (net (code "56") (name "Net-(JP3-2)") (class "Default")
      (node (ref "JP3") (pin "COM") (pinfunction "2_COM") (pintype "passive"))
      (node (ref "SRP3") (pin "1") (pinfunction "1_1") (pintype "passive"))
    )
    (net (code "57") (name "Net-(JP4-2)") (class "Default")
      (node (ref "JP4") (pin "COM") (pinfunction "2_COM") (pintype "passive"))
      (node (ref "SRP2") (pin "1") (pinfunction "1_1") (pintype "passive"))
    )
    (net (code "58") (name "Net-(JP6-2)") (class "Default")
      (node (ref "JP6") (pin "COM") (pinfunction "2_COM") (pintype "passive"))
      (node (ref "ULTRASONIC") (pin "1") (pinfunction "1_1") (pintype "passive"))
    )
    (net (code "59") (name "Net-(JP7-2)") (class "Default")
      (node (ref "JP7") (pin "COM") (pinfunction "2_COM") (pintype "passive"))
      (node (ref "SERVO_1") (pin "3") (pinfunction "3_3") (pintype "passive"))
      (node (ref "SERVO_2") (pin "3") (pinfunction "3_3") (pintype "passive"))
      (node (ref "SERVO_3") (pin "3") (pinfunction "3_3") (pintype "passive"))
    )
    (net (code "60") (name "Net-(JP8-2)") (class "Default")
      (node (ref "JP8") (pin "COM") (pinfunction "2_COM") (pintype "passive"))
      (node (ref "LF") (pin "1") (pinfunction "1_1") (pintype "passive"))
    )
    (net (code "61") (name "Net-(JP9-2)") (class "Default")
      (node (ref "JP9") (pin "COM") (pinfunction "2_COM") (pintype "passive"))
      (node (ref "OLED2") (pin "1") (pinfunction "1_1") (pintype "passive"))
      (node (ref "OLED_1") (pin "1") (pinfunction "1_1") (pintype "passive"))
    )
    (net (code "62") (name "Net-(JP10-2)") (class "Default")
      (node (ref "JP10") (pin "COM") (pinfunction "2_COM") (pintype "passive"))
      (node (ref "OLED2") (pin "2") (pinfunction "2_2") (pintype "passive"))
      (node (ref "OLED_1") (pin "2") (pinfunction "2_2") (pintype "passive"))
    )
    (net (code "63") (name "Net-(R9-Pad2)") (class "Default")
      (node (ref "R9") (pin "2") (pinfunction "2_2") (pintype "passive"))
      (node (ref "T1") (pin "B") (pinfunction "B_B") (pintype "passive"))
    )
    (net (code "64") (name "Net-(R11-Pad2)") (class "Default")
      (node (ref "R11") (pin "2") (pinfunction "2_2") (pintype "passive"))
      (node (ref "R12") (pin "1") (pinfunction "1_1") (pintype "passive"))
    )
    (net (code "65") (name "OC0A") (class "Default")
      (node (ref "EYFI_MEGA") (pin "47") (pinfunction "OC0A_47") (pintype "bidirectional"))
      (node (ref "PWM1") (pin "6") (pinfunction "6_6") (pintype "passive"))
    )
    (net (code "66") (name "OC0B") (class "Default")
      (node (ref "EYFI_MEGA") (pin "46") (pinfunction "OC0B_46") (pintype "bidirectional"))
      (node (ref "PWM1") (pin "7") (pinfunction "7_7") (pintype "passive"))
    )
    (net (code "67") (name "OC1A") (class "Default")
      (node (ref "EYFI_MEGA") (pin "44") (pinfunction "OC1A_44") (pintype "bidirectional"))
      (node (ref "PWM2") (pin "3") (pinfunction "3_3") (pintype "passive"))
    )
    (net (code "68") (name "OC1B") (class "Default")
      (node (ref "CAM") (pin "7") (pinfunction "7_7") (pintype "passive"))
      (node (ref "EYFI_MEGA") (pin "45") (pinfunction "OC1B_45") (pintype "bidirectional"))
      (node (ref "PWM1") (pin "8") (pinfunction "8_8") (pintype "passive"))
    )
    (net (code "69") (name "OC2A") (class "Default")
      (node (ref "EYFI_MEGA") (pin "43") (pinfunction "OC2A_43") (pintype "bidirectional"))
      (node (ref "PWM2") (pin "4") (pinfunction "4_4") (pintype "passive"))
    )
    (net (code "70") (name "OC2B") (class "Default")
      (node (ref "EYFI_MEGA") (pin "42") (pinfunction "OC2B_42") (pintype "bidirectional"))
      (node (ref "PWM2") (pin "5") (pinfunction "5_5") (pintype "passive"))
      (node (ref "R10") (pin "2") (pinfunction "2_2") (pintype "passive"))
    )
    (net (code "71") (name "OC3A") (class "Default")
      (node (ref "EYFI_MEGA") (pin "38") (pinfunction "OC3A_38") (pintype "bidirectional"))
      (node (ref "PWM2") (pin "9") (pinfunction "9_9") (pintype "passive"))
      (node (ref "R9") (pin "1") (pinfunction "1_1") (pintype "passive"))
    )
    (net (code "72") (name "OC4A") (class "Default")
      (node (ref "EYFI_MEGA") (pin "39") (pinfunction "OC4A_39") (pintype "bidirectional"))
      (node (ref "PWM2") (pin "8") (pinfunction "8_8") (pintype "passive"))
      (node (ref "SERVO_1") (pin "2") (pinfunction "2_2") (pintype "passive"))
    )
    (net (code "73") (name "OC4B") (class "Default")
      (node (ref "EYFI_MEGA") (pin "40") (pinfunction "OC4B_40") (pintype "bidirectional"))
      (node (ref "PWM2") (pin "7") (pinfunction "7_7") (pintype "passive"))
      (node (ref "SERVO_2") (pin "2") (pinfunction "2_2") (pintype "passive"))
    )
    (net (code "74") (name "OC4C") (class "Default")
      (node (ref "EYFI_MEGA") (pin "41") (pinfunction "OC4C_41") (pintype "bidirectional"))
      (node (ref "PWM2") (pin "6") (pinfunction "6_6") (pintype "passive"))
      (node (ref "SERVO_3") (pin "2") (pinfunction "2_2") (pintype "passive"))
    )
    (net (code "75") (name "OC5A") (class "Default")
      (node (ref "EYFI_MEGA") (pin "48") (pinfunction "OC5A_48") (pintype "bidirectional"))
      (node (ref "MTR_CTR") (pin "5") (pinfunction "5_5") (pintype "passive"))
      (node (ref "PWM1") (pin "5") (pinfunction "5_5") (pintype "passive"))
    )
    (net (code "76") (name "OC5B") (class "Default")
      (node (ref "EYFI_MEGA") (pin "49") (pinfunction "OC5B_49") (pintype "bidirectional"))
      (node (ref "MTR_CTR") (pin "6") (pinfunction "6_6") (pintype "passive"))
      (node (ref "PWM1") (pin "4") (pinfunction "4_4") (pintype "passive"))
    )
    (net (code "77") (name "OC5C") (class "Default")
      (node (ref "EYFI_MEGA") (pin "50") (pinfunction "OC5C_50") (pintype "bidirectional"))
      (node (ref "PWM1") (pin "3") (pinfunction "3_3") (pintype "passive"))
    )
    (net (code "78") (name "PA0") (class "Default")
      (node (ref "CAM") (pin "16") (pinfunction "16_16") (pintype "passive"))
      (node (ref "EYFI_MEGA") (pin "102") (pinfunction "PA0_102") (pintype "bidirectional"))
      (node (ref "GPIO2") (pin "3") (pinfunction "3_3") (pintype "passive"))
    )
    (net (code "79") (name "PA1") (class "Default")
      (node (ref "CAM") (pin "15") (pinfunction "15_15") (pintype "passive"))
      (node (ref "EYFI_MEGA") (pin "101") (pinfunction "PA1_101") (pintype "bidirectional"))
      (node (ref "GPIO2") (pin "4") (pinfunction "4_4") (pintype "passive"))
    )
    (net (code "80") (name "PA2") (class "Default")
      (node (ref "CAM") (pin "14") (pinfunction "14_14") (pintype "passive"))
      (node (ref "EYFI_MEGA") (pin "100") (pinfunction "PA2_100") (pintype "bidirectional"))
      (node (ref "GPIO2") (pin "5") (pinfunction "5_5") (pintype "passive"))
    )
    (net (code "81") (name "PA3") (class "Default")
      (node (ref "CAM") (pin "13") (pinfunction "13_13") (pintype "passive"))
      (node (ref "EYFI_MEGA") (pin "99") (pinfunction "PA3_99") (pintype "bidirectional"))
      (node (ref "GPIO2") (pin "6") (pinfunction "6_6") (pintype "passive"))
    )
    (net (code "82") (name "PA4") (class "Default")
      (node (ref "CAM") (pin "12") (pinfunction "12_12") (pintype "passive"))
      (node (ref "EYFI_MEGA") (pin "98") (pinfunction "PA4_98") (pintype "bidirectional"))
      (node (ref "GPIO2") (pin "7") (pinfunction "7_7") (pintype "passive"))
    )
    (net (code "83") (name "PA5") (class "Default")
      (node (ref "CAM") (pin "11") (pinfunction "11_11") (pintype "passive"))
      (node (ref "EYFI_MEGA") (pin "97") (pinfunction "PA5_97") (pintype "bidirectional"))
      (node (ref "GPIO2") (pin "8") (pinfunction "8_8") (pintype "passive"))
    )
    (net (code "84") (name "PA6") (class "Default")
      (node (ref "CAM") (pin "10") (pinfunction "10_10") (pintype "passive"))
      (node (ref "EYFI_MEGA") (pin "96") (pinfunction "PA6_96") (pintype "bidirectional"))
      (node (ref "GPIO2") (pin "9") (pinfunction "9_9") (pintype "passive"))
    )
    (net (code "85") (name "PA7") (class "Default")
      (node (ref "CAM") (pin "9") (pinfunction "9_9") (pintype "passive"))
      (node (ref "EYFI_MEGA") (pin "95") (pinfunction "PA7_95") (pintype "bidirectional"))
      (node (ref "GPIO2") (pin "10") (pinfunction "10_10") (pintype "passive"))
    )
    (net (code "86") (name "PB1") (class "Default")
      (node (ref "EYFI_MEGA") (pin "75") (pinfunction "SCK_PB1_75") (pintype "bidirectional"))
      (node (ref "SPI1") (pin "8") (pinfunction "8_8") (pintype "passive"))
    )
    (net (code "87") (name "PB2") (class "Default")
      (node (ref "EYFI_MEGA") (pin "77") (pinfunction "MOSI_PB2_77") (pintype "bidirectional"))
      (node (ref "SPI1") (pin "6") (pinfunction "6_6") (pintype "passive"))
    )
    (net (code "88") (name "PB3") (class "Default")
      (node (ref "EYFI_MEGA") (pin "79") (pinfunction "MISO_PB3_79") (pintype "bidirectional"))
      (node (ref "SPI1") (pin "4") (pinfunction "4_4") (pintype "passive"))
    )
    (net (code "89") (name "PC0") (class "Default")
      (node (ref "EYFI_MEGA") (pin "6") (pinfunction "PC0_6") (pintype "bidirectional"))
      (node (ref "GPIO1") (pin "6") (pinfunction "6_6") (pintype "passive"))
      (node (ref "R1") (pin "1") (pinfunction "1_1") (pintype "passive"))
    )
    (net (code "90") (name "PC1") (class "Default")
      (node (ref "EYFI_MEGA") (pin "5") (pinfunction "PC1_5") (pintype "bidirectional"))
      (node (ref "GPIO1") (pin "5") (pinfunction "5_5") (pintype "passive"))
      (node (ref "R2") (pin "1") (pinfunction "1_1") (pintype "passive"))
    )
    (net (code "91") (name "PC2") (class "Default")
      (node (ref "EYFI_MEGA") (pin "4") (pinfunction "PC2_4") (pintype "bidirectional"))
      (node (ref "GPIO1") (pin "4") (pinfunction "4_4") (pintype "passive"))
      (node (ref "R3") (pin "1") (pinfunction "1_1") (pintype "passive"))
    )
    (net (code "92") (name "PC3") (class "Default")
      (node (ref "EYFI_MEGA") (pin "3") (pinfunction "PC3_3") (pintype "bidirectional"))
      (node (ref "GPIO1") (pin "3") (pinfunction "3_3") (pintype "passive"))
      (node (ref "R4") (pin "1") (pinfunction "1_1") (pintype "passive"))
    )
    (net (code "93") (name "PC4") (class "Default")
      (node (ref "EYFI_MEGA") (pin "85") (pinfunction "PC4_85") (pintype "bidirectional"))
      (node (ref "GPIO2") (pin "20") (pinfunction "20_20") (pintype "passive"))
      (node (ref "R5") (pin "1") (pinfunction "1_1") (pintype "passive"))
    )
    (net (code "94") (name "PC5") (class "Default")
      (node (ref "EYFI_MEGA") (pin "86") (pinfunction "PC5_86") (pintype "bidirectional"))
      (node (ref "GPIO2") (pin "19") (pinfunction "19_19") (pintype "passive"))
      (node (ref "R6") (pin "2") (pinfunction "2_2") (pintype "passive"))
    )
    (net (code "95") (name "PC6") (class "Default")
      (node (ref "EYFI_MEGA") (pin "87") (pinfunction "PC6_87") (pintype "bidirectional"))
      (node (ref "GPIO2") (pin "18") (pinfunction "18_18") (pintype "passive"))
      (node (ref "R7") (pin "2") (pinfunction "2_2") (pintype "passive"))
    )
    (net (code "96") (name "PC7") (class "Default")
      (node (ref "EYFI_MEGA") (pin "88") (pinfunction "PC7_88") (pintype "bidirectional"))
      (node (ref "GPIO2") (pin "17") (pinfunction "17_17") (pintype "passive"))
      (node (ref "R8") (pin "2") (pinfunction "2_2") (pintype "passive"))
    )
    (net (code "97") (name "PD0") (class "Default")
      (node (ref "EYFI_MEGA") (pin "107") (pinfunction "SCL_PD0_107") (pintype "bidirectional"))
      (node (ref "I2C") (pin "6") (pinfunction "6_6") (pintype "passive"))
    )
    (net (code "98") (name "PD1") (class "Default")
      (node (ref "EYFI_MEGA") (pin "109") (pinfunction "SDA_PD1_109") (pintype "bidirectional"))
      (node (ref "I2C") (pin "4") (pinfunction "4_4") (pintype "passive"))
    )
    (net (code "99") (name "PD4") (class "Default")
      (node (ref "EYFI_MEGA") (pin "12") (pinfunction "PD4_12") (pintype "bidirectional"))
      (node (ref "GPIO1") (pin "12") (pinfunction "12_12") (pintype "passive"))
      (node (ref "MTR_CTR") (pin "1") (pinfunction "1_1") (pintype "passive"))
    )
    (net (code "100") (name "PD5") (class "Default")
      (node (ref "EYFI_MEGA") (pin "11") (pinfunction "PD5_11") (pintype "bidirectional"))
      (node (ref "GPIO1") (pin "11") (pinfunction "11_11") (pintype "passive"))
      (node (ref "MTR_CTR") (pin "2") (pinfunction "2_2") (pintype "passive"))
    )
    (net (code "101") (name "PD6") (class "Default")
      (node (ref "EYFI_MEGA") (pin "10") (pinfunction "PD6_10") (pintype "bidirectional"))
      (node (ref "GPIO1") (pin "10") (pinfunction "10_10") (pintype "passive"))
      (node (ref "MTR_CTR") (pin "3") (pinfunction "3_3") (pintype "passive"))
    )
    (net (code "102") (name "PD7") (class "Default")
      (node (ref "EYFI_MEGA") (pin "9") (pinfunction "PD7_9") (pintype "bidirectional"))
      (node (ref "GPIO1") (pin "9") (pinfunction "9_9") (pintype "passive"))
      (node (ref "MTR_CTR") (pin "4") (pinfunction "4_4") (pintype "passive"))
    )
    (net (code "103") (name "PE2") (class "Default")
      (node (ref "EYFI_MEGA") (pin "20") (pinfunction "PE2_20") (pintype "bidirectional"))
      (node (ref "GPIO1") (pin "20") (pinfunction "20_20") (pintype "passive"))
    )
    (net (code "104") (name "PG0") (class "Default")
      (node (ref "EYFI_MEGA") (pin "8") (pinfunction "PG0_8") (pintype "bidirectional"))
      (node (ref "GPIO1") (pin "8") (pinfunction "8_8") (pintype "passive"))
    )
    (net (code "105") (name "PG1") (class "Default")
      (node (ref "EYFI_MEGA") (pin "7") (pinfunction "PG1_7") (pintype "bidirectional"))
      (node (ref "GPIO1") (pin "7") (pinfunction "7_7") (pintype "passive"))
    )
    (net (code "106") (name "PG2") (class "Default")
      (node (ref "EYFI_MEGA") (pin "94") (pinfunction "PG2_94") (pintype "bidirectional"))
      (node (ref "GPIO2") (pin "11") (pinfunction "11_11") (pintype "passive"))
      (node (ref "ULTRASONIC") (pin "2") (pinfunction "2_2") (pintype "passive"))
    )
    (net (code "107") (name "PH2") (class "Default")
      (node (ref "EYFI_MEGA") (pin "19") (pinfunction "PH2_19") (pintype "bidirectional"))
      (node (ref "GPIO1") (pin "19") (pinfunction "19_19") (pintype "passive"))
    )
    (net (code "108") (name "PH7") (class "Default")
      (node (ref "EYFI_MEGA") (pin "18") (pinfunction "PH7_18") (pintype "bidirectional"))
      (node (ref "GPIO1") (pin "18") (pinfunction "18_18") (pintype "passive"))
    )
    (net (code "109") (name "PJ2") (class "Default")
      (node (ref "EYFI_MEGA") (pin "89") (pinfunction "PJ2_89") (pintype "bidirectional"))
      (node (ref "GPIO2") (pin "16") (pinfunction "16_16") (pintype "passive"))
    )
    (net (code "110") (name "PJ3") (class "Default")
      (node (ref "EYFI_MEGA") (pin "90") (pinfunction "PJ3_90") (pintype "bidirectional"))
      (node (ref "GPIO2") (pin "15") (pinfunction "15_15") (pintype "passive"))
    )
    (net (code "111") (name "PJ4") (class "Default")
      (node (ref "EYFI_MEGA") (pin "91") (pinfunction "PJ4_91") (pintype "bidirectional"))
      (node (ref "GPIO2") (pin "14") (pinfunction "14_14") (pintype "passive"))
    )
    (net (code "112") (name "PJ5") (class "Default")
      (node (ref "EYFI_MEGA") (pin "92") (pinfunction "PJ5_92") (pintype "bidirectional"))
      (node (ref "GPIO2") (pin "13") (pinfunction "13_13") (pintype "passive"))
    )
    (net (code "113") (name "PJ6") (class "Default")
      (node (ref "EYFI_MEGA") (pin "93") (pinfunction "PJ6_93") (pintype "bidirectional"))
      (node (ref "GPIO2") (pin "12") (pinfunction "12_12") (pintype "passive"))
      (node (ref "ULTRASONIC") (pin "3") (pinfunction "3_3") (pintype "passive"))
    )
    (net (code "114") (name "PL0") (class "Default")
      (node (ref "EYFI_MEGA") (pin "17") (pinfunction "PL0_17") (pintype "bidirectional"))
      (node (ref "GPIO1") (pin "17") (pinfunction "17_17") (pintype "passive"))
    )
    (net (code "115") (name "PL1") (class "Default")
      (node (ref "EYFI_MEGA") (pin "16") (pinfunction "PL1_16") (pintype "bidirectional"))
      (node (ref "GPIO1") (pin "16") (pinfunction "16_16") (pintype "passive"))
    )
    (net (code "116") (name "PL2") (class "Default")
      (node (ref "EYFI_MEGA") (pin "15") (pinfunction "PL2_15") (pintype "bidirectional"))
      (node (ref "GPIO1") (pin "15") (pinfunction "15_15") (pintype "passive"))
    )
    (net (code "117") (name "PL6") (class "Default")
      (node (ref "EYFI_MEGA") (pin "14") (pinfunction "PL6_14") (pintype "bidirectional"))
      (node (ref "GPIO1") (pin "14") (pinfunction "14_14") (pintype "passive"))
    )
    (net (code "118") (name "PL7") (class "Default")
      (node (ref "EYFI_MEGA") (pin "13") (pinfunction "PL7_13") (pintype "bidirectional"))
      (node (ref "GPIO1") (pin "13") (pinfunction "13_13") (pintype "passive"))
    )
    (net (code "119") (name "RST") (class "Default")
      (node (ref "EYFI_MEGA") (pin "37") (pinfunction "RESET_37") (pintype "bidirectional"))
      (node (ref "PWM2") (pin "10") (pinfunction "10_10") (pintype "passive"))
    )
    (net (code "120") (name "RX1") (class "Default")
      (node (ref "CAM") (pin "5") (pinfunction "5_5") (pintype "passive"))
      (node (ref "EYFI_MEGA") (pin "29") (pinfunction "RX1_29") (pintype "bidirectional"))
      (node (ref "UART") (pin "7") (pinfunction "7_7") (pintype "passive"))
    )
    (net (code "121") (name "RX2") (class "Default")
      (node (ref "EYFI_MEGA") (pin "27") (pinfunction "RX2_27") (pintype "bidirectional"))
      (node (ref "UART") (pin "5") (pinfunction "5_5") (pintype "passive"))
    )
    (net (code "122") (name "RX3") (class "Default")
      (node (ref "EYFI_MEGA") (pin "25") (pinfunction "RX3_25") (pintype "bidirectional"))
      (node (ref "UART") (pin "3") (pinfunction "3_3") (pintype "passive"))
    )
    (net (code "123") (name "SCK") (class "Default")
      (node (ref "EYFI_MEGA") (pin "76") (pinfunction "SCK_PB1_76") (pintype "bidirectional"))
      (node (ref "SPI1") (pin "7") (pinfunction "7_7") (pintype "passive"))
    )
    (net (code "124") (name "SCL") (class "Default")
      (node (ref "CAM") (pin "3") (pinfunction "3_3") (pintype "passive"))
      (node (ref "EYFI_MEGA") (pin "108") (pinfunction "SCL_PD0_108") (pintype "bidirectional"))
      (node (ref "GY-87") (pin "4") (pinfunction "4_4") (pintype "passive"))
      (node (ref "I2C") (pin "5") (pinfunction "5_5") (pintype "passive"))
      (node (ref "I2C1") (pin "3") (pinfunction "3_3") (pintype "passive"))
      (node (ref "I2C2") (pin "3") (pinfunction "3_3") (pintype "passive"))
      (node (ref "LF") (pin "3") (pinfunction "3_3") (pintype "passive"))
      (node (ref "OLED2") (pin "3") (pinfunction "3_3") (pintype "passive"))
      (node (ref "OLED_1") (pin "3") (pinfunction "3_3") (pintype "passive"))
    )
    (net (code "125") (name "SDA") (class "Default")
      (node (ref "CAM") (pin "4") (pinfunction "4_4") (pintype "passive"))
      (node (ref "EYFI_MEGA") (pin "110") (pinfunction "SDA_PD1_110") (pintype "bidirectional"))
      (node (ref "GY-87") (pin "5") (pinfunction "5_5") (pintype "passive"))
      (node (ref "I2C") (pin "3") (pinfunction "3_3") (pintype "passive"))
      (node (ref "I2C1") (pin "2") (pinfunction "2_2") (pintype "passive"))
      (node (ref "I2C2") (pin "2") (pinfunction "2_2") (pintype "passive"))
      (node (ref "LF") (pin "2") (pinfunction "2_2") (pintype "passive"))
      (node (ref "OLED2") (pin "4") (pinfunction "4_4") (pintype "passive"))
      (node (ref "OLED_1") (pin "4") (pinfunction "4_4") (pintype "passive"))
    )
    (net (code "126") (name "SS0{slash}PB0") (class "Default")
      (node (ref "EYFI_MEGA") (pin "73") (pinfunction "SS0_PB0_73") (pintype "bidirectional"))
      (node (ref "SPI1") (pin "10") (pinfunction "10_10") (pintype "passive"))
    )
    (net (code "127") (name "SS1{slash}PJ7") (class "Default")
      (node (ref "EYFI_MEGA") (pin "74") (pinfunction "SS1_PJ7_74") (pintype "bidirectional"))
      (node (ref "SPI1") (pin "9") (pinfunction "9_9") (pintype "passive"))
    )
    (net (code "128") (name "TX1") (class "Default")
      (node (ref "EYFI_MEGA") (pin "30") (pinfunction "TX1_30") (pintype "bidirectional"))
      (node (ref "UART") (pin "8") (pinfunction "8_8") (pintype "passive"))
    )
    (net (code "129") (name "TX2") (class "Default")
      (node (ref "EYFI_MEGA") (pin "28") (pinfunction "TX2_28") (pintype "bidirectional"))
      (node (ref "UART") (pin "6") (pinfunction "6_6") (pintype "passive"))
    )
    (net (code "130") (name "TX3") (class "Default")
      (node (ref "EYFI_MEGA") (pin "26") (pinfunction "TX3_26") (pintype "bidirectional"))
      (node (ref "UART") (pin "4") (pinfunction "4_4") (pintype "passive"))
    )
    (net (code "131") (name "XCLK") (class "Default")
      (node (ref "CAM") (pin "8") (pinfunction "8_8") (pintype "passive"))
      (node (ref "R10") (pin "1") (pinfunction "1_1") (pintype "passive"))
      (node (ref "R11") (pin "1") (pinfunction "1_1") (pintype "passive"))
    )
    (net (code "132") (name "unconnected-(CAM-Pad6)") (class "Default")
      (node (ref "CAM") (pin "6") (pinfunction "6_6") (pintype "passive"))
    )
    (net (code "133") (name "unconnected-(GY-87-Pad2)") (class "Default")
      (node (ref "GY-87") (pin "2") (pinfunction "2_2") (pintype "passive"))
    )
    (net (code "134") (name "unconnected-(GY-87-Pad6)") (class "Default")
      (node (ref "GY-87") (pin "6") (pinfunction "6_6") (pintype "passive"))
    )
    (net (code "135") (name "unconnected-(GY-87-Pad7)") (class "Default")
      (node (ref "GY-87") (pin "7") (pinfunction "7_7") (pintype "passive"))
    )
    (net (code "136") (name "unconnected-(GY-87-Pad8)") (class "Default")
      (node (ref "GY-87") (pin "8") (pinfunction "8_8") (pintype "passive"))
    )
    (net (code "137") (name "unconnected-(JP1-3-PadNC)") (class "Default")
      (node (ref "JP1") (pin "NC") (pinfunction "3_NC") (pintype "passive"))
    )
    (net (code "138") (name "unconnected-(JP2-3-PadNC)") (class "Default")
      (node (ref "JP2") (pin "NC") (pinfunction "3_NC") (pintype "passive"))
    )
    (net (code "139") (name "unconnected-(JP3-3-PadNC)") (class "Default")
      (node (ref "JP3") (pin "NC") (pinfunction "3_NC") (pintype "passive"))
    )
    (net (code "140") (name "unconnected-(JP4-3-PadNC)") (class "Default")
      (node (ref "JP4") (pin "NC") (pinfunction "3_NC") (pintype "passive"))
    )
    (net (code "141") (name "unconnected-(JP5-3-PadNC)") (class "Default")
      (node (ref "JP5") (pin "NC") (pinfunction "3_NC") (pintype "passive"))
    )
    (net (code "142") (name "unconnected-(JP6-3-PadNC)") (class "Default")
      (node (ref "JP6") (pin "NC") (pinfunction "3_NC") (pintype "passive"))
    )
    (net (code "143") (name "unconnected-(JP7-3-PadNC)") (class "Default")
      (node (ref "JP7") (pin "NC") (pinfunction "3_NC") (pintype "passive"))
    )
    (net (code "144") (name "unconnected-(JP8-3-PadNC)") (class "Default")
      (node (ref "JP8") (pin "NC") (pinfunction "3_NC") (pintype "passive"))
    )
    (net (code "145") (name "unconnected-(JP9-3-PadNC)") (class "Default")
      (node (ref "JP9") (pin "NC") (pinfunction "3_NC") (pintype "passive"))
    )
    (net (code "146") (name "unconnected-(JP10-3-PadNC)") (class "Default")
      (node (ref "JP10") (pin "NC") (pinfunction "3_NC") (pintype "passive"))
    )
    (net (code "147") (name "unconnected-(UART-Pad9)") (class "Default")
      (node (ref "UART") (pin "9") (pinfunction "9_9") (pintype "passive"))
    )
    (net (code "148") (name "unconnected-(UART-Pad10)") (class "Default")
      (node (ref "UART") (pin "10") (pinfunction "10_10") (pintype "passive"))
    )
  )
)
